# Aux_Board_V2_1.net
KiCad netlist of a schematic drawn in EAGLE
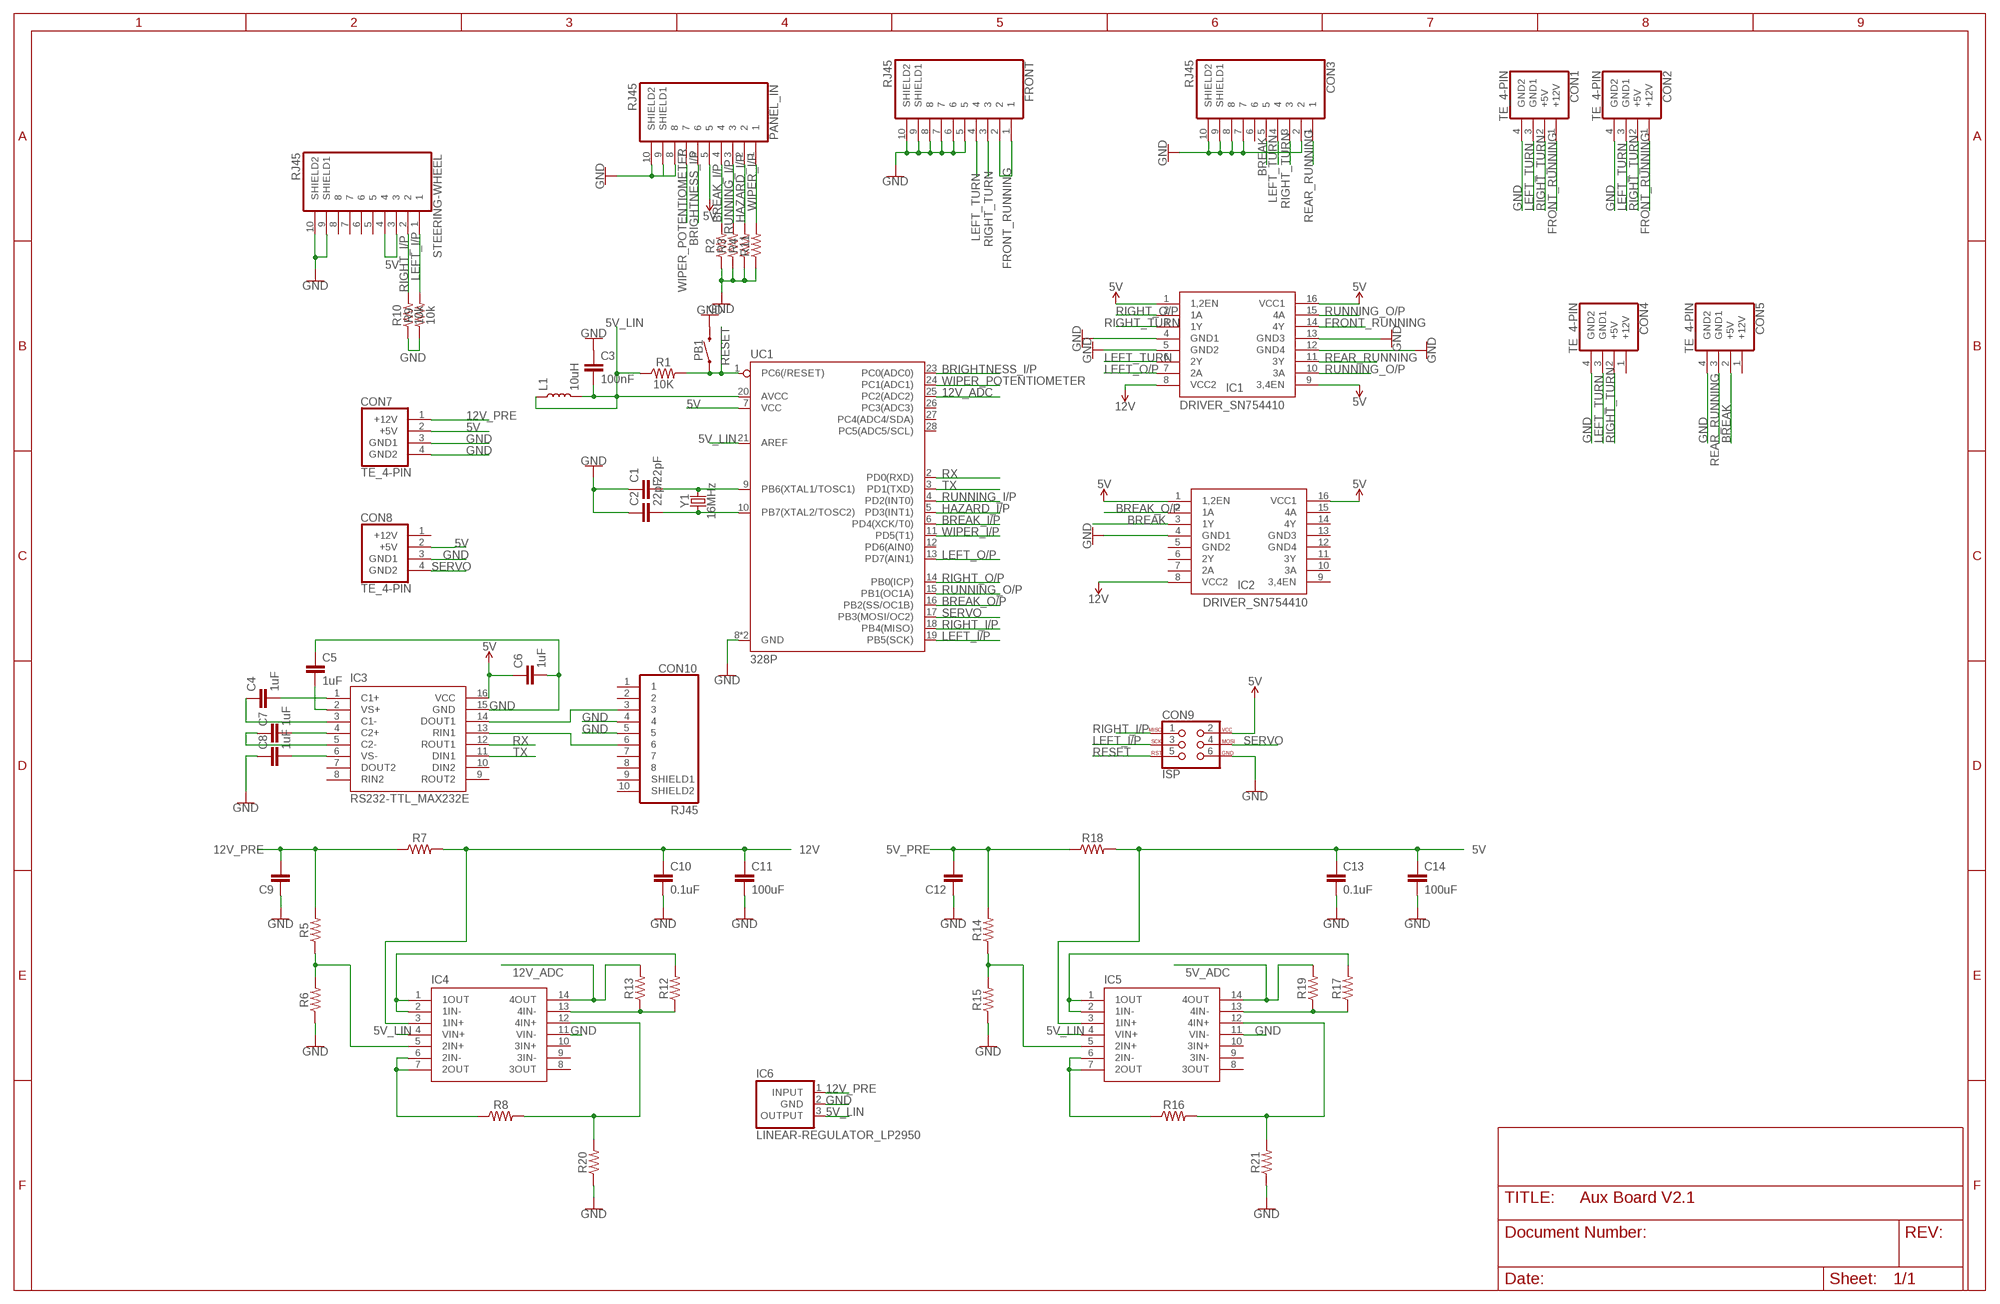
[diagram p0: schematic, sheet 1]

(export (version "E")
  (design (tool "Eeschema 10.0.6"))
  (components
    (comp (ref "C1")
      (value "22pF")
      (footprint "eagle-import:0805")
      (libsource (lib "eagle-import") (part "CAPACITOR_0805"))
    )
    (comp (ref "C2")
      (value "22pF")
      (footprint "eagle-import:0805")
      (libsource (lib "eagle-import") (part "CAPACITOR_0805"))
    )
    (comp (ref "C3")
      (value "100nF")
      (footprint "eagle-import:0805")
      (libsource (lib "eagle-import") (part "CAPACITOR_0805"))
    )
    (comp (ref "C4")
      (value "1uF")
      (footprint "eagle-import:0805")
      (libsource (lib "eagle-import") (part "CAPACITOR_0805"))
    )
    (comp (ref "C5")
      (value "1uF")
      (footprint "eagle-import:0805")
      (libsource (lib "eagle-import") (part "CAPACITOR_0805"))
    )
    (comp (ref "C6")
      (value "1uF")
      (footprint "eagle-import:0805")
      (libsource (lib "eagle-import") (part "CAPACITOR_0805"))
    )
    (comp (ref "C7")
      (value "1uF")
      (footprint "eagle-import:0805")
      (libsource (lib "eagle-import") (part "CAPACITOR_0805"))
    )
    (comp (ref "C8")
      (value "1uF")
      (footprint "eagle-import:0805")
      (libsource (lib "eagle-import") (part "CAPACITOR_0805"))
    )
    (comp (ref "C9")
      (value "CAPACITOR_0805")
      (footprint "eagle-import:0805")
      (libsource (lib "eagle-import") (part "CAPACITOR_0805"))
    )
    (comp (ref "C10")
      (value "0.1uF")
      (footprint "eagle-import:0805")
      (libsource (lib "eagle-import") (part "CAPACITOR_0805"))
    )
    (comp (ref "C11")
      (value "100uF")
      (footprint "eagle-import:0805")
      (libsource (lib "eagle-import") (part "CAPACITOR_0805"))
    )
    (comp (ref "C12")
      (value "CAPACITOR_0805")
      (footprint "eagle-import:0805")
      (libsource (lib "eagle-import") (part "CAPACITOR_0805"))
    )
    (comp (ref "C13")
      (value "0.1uF")
      (footprint "eagle-import:0805")
      (libsource (lib "eagle-import") (part "CAPACITOR_0805"))
    )
    (comp (ref "C14")
      (value "100uF")
      (footprint "eagle-import:0805")
      (libsource (lib "eagle-import") (part "CAPACITOR_0805"))
    )
    (comp (ref "CON1")
      (value "TE_4-PIN")
      (footprint "eagle-import:TE_4-PIN")
      (libsource (lib "eagle-import") (part "TE_4-PIN"))
    )
    (comp (ref "CON2")
      (value "TE_4-PIN")
      (footprint "eagle-import:TE_4-PIN")
      (libsource (lib "eagle-import") (part "TE_4-PIN"))
    )
    (comp (ref "CON3")
      (value "RJ45")
      (footprint "eagle-import:RJ45")
      (libsource (lib "eagle-import") (part "RJ45"))
    )
    (comp (ref "CON4")
      (value "TE_4-PIN")
      (footprint "eagle-import:TE_4-PIN")
      (libsource (lib "eagle-import") (part "TE_4-PIN"))
    )
    (comp (ref "CON5")
      (value "TE_4-PIN")
      (footprint "eagle-import:TE_4-PIN")
      (libsource (lib "eagle-import") (part "TE_4-PIN"))
    )
    (comp (ref "CON7")
      (value "TE_4-PIN")
      (footprint "eagle-import:TE_4-PIN")
      (libsource (lib "eagle-import") (part "TE_4-PIN"))
    )
    (comp (ref "CON8")
      (value "TE_4-PIN")
      (footprint "eagle-import:TE_4-PIN")
      (libsource (lib "eagle-import") (part "TE_4-PIN"))
    )
    (comp (ref "CON9")
      (value "ISP")
      (footprint "eagle-import:ISP_CONNECTOR")
      (libsource (lib "eagle-import") (part "ISP"))
    )
    (comp (ref "CON10")
      (value "RJ45")
      (footprint "eagle-import:RJ45")
      (libsource (lib "eagle-import") (part "RJ45"))
    )
    (comp (ref "FRONT")
      (value "RJ45")
      (footprint "eagle-import:RJ45")
      (libsource (lib "eagle-import") (part "RJ45"))
    )
    (comp (ref "IC1")
      (value "DRIVER_SN754410")
      (footprint "eagle-import:DIP16")
      (libsource (lib "eagle-import") (part "DRIVER_SN754410"))
    )
    (comp (ref "IC2")
      (value "DRIVER_SN754410")
      (footprint "eagle-import:DIP16")
      (libsource (lib "eagle-import") (part "DRIVER_SN754410"))
    )
    (comp (ref "IC3")
      (value "RS232-TTL_MAX232E")
      (footprint "eagle-import:DIP16")
      (libsource (lib "eagle-import") (part "RS232-TTL_MAX232E"))
    )
    (comp (ref "IC4")
      (value "OP-AMP_QUAD")
      (footprint "eagle-import:DIP14")
      (libsource (lib "eagle-import") (part "OP-AMP_QUAD"))
    )
    (comp (ref "IC5")
      (value "OP-AMP_QUAD")
      (footprint "eagle-import:DIP14")
      (libsource (lib "eagle-import") (part "OP-AMP_QUAD"))
    )
    (comp (ref "IC6")
      (value "LINEAR-REGULATOR_LP2950")
      (footprint "eagle-import:TO92")
      (libsource (lib "eagle-import") (part "LINEAR-REGULATOR_LP2950"))
    )
    (comp (ref "L1")
      (value "10uH")
      (footprint "eagle-import:0805")
      (libsource (lib "eagle-import") (part "INDUCTOR_0805"))
    )
    (comp (ref "PANEL_IN")
      (value "RJ45")
      (footprint "eagle-import:RJ45")
      (libsource (lib "eagle-import") (part "RJ45"))
    )
    (comp (ref "PB1")
      (value "PUSHBUTTON")
      (footprint "eagle-import:PUSHBUTTON")
      (libsource (lib "eagle-import") (part "PUSHBUTTON"))
    )
    (comp (ref "R1")
      (value "10K")
      (footprint "eagle-import:0805")
      (libsource (lib "eagle-import") (part "RESISTOR_0805"))
    )
    (comp (ref "R2")
      (value "RESISTOR_0805")
      (footprint "eagle-import:0805")
      (libsource (lib "eagle-import") (part "RESISTOR_0805"))
    )
    (comp (ref "R3")
      (value "RESISTOR_0805")
      (footprint "eagle-import:0805")
      (libsource (lib "eagle-import") (part "RESISTOR_0805"))
    )
    (comp (ref "R4")
      (value "RESISTOR_0805")
      (footprint "eagle-import:0805")
      (libsource (lib "eagle-import") (part "RESISTOR_0805"))
    )
    (comp (ref "R5")
      (value "RESISTOR_0805")
      (footprint "eagle-import:0805")
      (libsource (lib "eagle-import") (part "RESISTOR_0805"))
    )
    (comp (ref "R6")
      (value "RESISTOR_0805")
      (footprint "eagle-import:0805")
      (libsource (lib "eagle-import") (part "RESISTOR_0805"))
    )
    (comp (ref "R7")
      (value "RESISTOR_1210")
      (footprint "eagle-import:1210")
      (libsource (lib "eagle-import") (part "RESISTOR_1210"))
    )
    (comp (ref "R8")
      (value "RESISTOR_0805")
      (footprint "eagle-import:0805")
      (libsource (lib "eagle-import") (part "RESISTOR_0805"))
    )
    (comp (ref "R9")
      (value "10k")
      (footprint "eagle-import:0805")
      (libsource (lib "eagle-import") (part "RESISTOR_0805"))
    )
    (comp (ref "R10")
      (value "10k")
      (footprint "eagle-import:0805")
      (libsource (lib "eagle-import") (part "RESISTOR_0805"))
    )
    (comp (ref "R11")
      (value "RESISTOR_0805")
      (footprint "eagle-import:0805")
      (libsource (lib "eagle-import") (part "RESISTOR_0805"))
    )
    (comp (ref "R12")
      (value "RESISTOR_0805")
      (footprint "eagle-import:0805")
      (libsource (lib "eagle-import") (part "RESISTOR_0805"))
    )
    (comp (ref "R13")
      (value "RESISTOR_0805")
      (footprint "eagle-import:0805")
      (libsource (lib "eagle-import") (part "RESISTOR_0805"))
    )
    (comp (ref "R14")
      (value "RESISTOR_0805")
      (footprint "eagle-import:0805")
      (libsource (lib "eagle-import") (part "RESISTOR_0805"))
    )
    (comp (ref "R15")
      (value "RESISTOR_0805")
      (footprint "eagle-import:0805")
      (libsource (lib "eagle-import") (part "RESISTOR_0805"))
    )
    (comp (ref "R16")
      (value "RESISTOR_0805")
      (footprint "eagle-import:0805")
      (libsource (lib "eagle-import") (part "RESISTOR_0805"))
    )
    (comp (ref "R17")
      (value "RESISTOR_0805")
      (footprint "eagle-import:0805")
      (libsource (lib "eagle-import") (part "RESISTOR_0805"))
    )
    (comp (ref "R18")
      (value "RESISTOR_1210")
      (footprint "eagle-import:1210")
      (libsource (lib "eagle-import") (part "RESISTOR_1210"))
    )
    (comp (ref "R19")
      (value "RESISTOR_0805")
      (footprint "eagle-import:0805")
      (libsource (lib "eagle-import") (part "RESISTOR_0805"))
    )
    (comp (ref "R20")
      (value "RESISTOR_0805")
      (footprint "eagle-import:0805")
      (libsource (lib "eagle-import") (part "RESISTOR_0805"))
    )
    (comp (ref "R21")
      (value "RESISTOR_0805")
      (footprint "eagle-import:0805")
      (libsource (lib "eagle-import") (part "RESISTOR_0805"))
    )
    (comp (ref "STEERING-WHEEL")
      (value "RJ45")
      (footprint "eagle-import:RJ45")
      (libsource (lib "eagle-import") (part "RJ45"))
    )
    (comp (ref "UC1")
      (value "328P")
      (footprint "eagle-import:DIP28")
      (libsource (lib "eagle-import") (part "ATMEGA328P_DIP28"))
    )
    (comp (ref "Y1")
      (value "16MHz")
      (footprint "eagle-import:HC49US")
      (libsource (lib "eagle-import") (part "CRYSTAL-16MHZPTH-HC49US"))
    )
  )
  (nets
    (net (code "1") (name "/5V_ADC") (class "Default")
      (node (ref "IC5") (pin "14") (pinfunction "4OUT_14") (pintype "bidirectional"))
      (node (ref "R19") (pin "2") (pinfunction "2_2") (pintype "passive"))
    )
    (net (code "2") (name "/5V_LIN") (class "Default")
      (node (ref "C3") (pin "2") (pinfunction "2_2") (pintype "passive"))
      (node (ref "IC4") (pin "4") (pinfunction "VIN+_4") (pintype "bidirectional"))
      (node (ref "IC5") (pin "4") (pinfunction "VIN+_4") (pintype "bidirectional"))
      (node (ref "IC6") (pin "3") (pinfunction "OUTPUT_3") (pintype "bidirectional"))
      (node (ref "L1") (pin "1") (pinfunction "1_1") (pintype "passive"))
      (node (ref "L1") (pin "2") (pinfunction "2_2") (pintype "passive"))
      (node (ref "R1") (pin "1") (pinfunction "1_1") (pintype "passive"))
      (node (ref "UC1") (pin "20") (pinfunction "AVCC_20") (pintype "bidirectional"))
      (node (ref "UC1") (pin "21") (pinfunction "AREF_21") (pintype "bidirectional"))
    )
    (net (code "3") (name "/5V_PRE") (class "Default")
      (node (ref "C12") (pin "2") (pinfunction "2_2") (pintype "passive"))
      (node (ref "R14") (pin "2") (pinfunction "2_2") (pintype "passive"))
      (node (ref "R18") (pin "1") (pinfunction "1_1") (pintype "passive"))
    )
    (net (code "4") (name "/12V_ADC") (class "Default")
      (node (ref "IC4") (pin "14") (pinfunction "4OUT_14") (pintype "bidirectional"))
      (node (ref "R13") (pin "2") (pinfunction "2_2") (pintype "passive"))
      (node (ref "UC1") (pin "25") (pinfunction "PC2(ADC2)_25") (pintype "bidirectional"))
    )
    (net (code "5") (name "/12V_PRE") (class "Default")
      (node (ref "C9") (pin "2") (pinfunction "2_2") (pintype "passive"))
      (node (ref "CON7") (pin "1") (pinfunction "+12V_1") (pintype "passive"))
      (node (ref "IC6") (pin "1") (pinfunction "INPUT_1") (pintype "bidirectional"))
      (node (ref "R5") (pin "2") (pinfunction "2_2") (pintype "passive"))
      (node (ref "R7") (pin "1") (pinfunction "1_1") (pintype "passive"))
    )
    (net (code "6") (name "/BREAK") (class "Default")
      (node (ref "CON3") (pin "5") (pinfunction "5_5") (pintype "passive"))
      (node (ref "CON5") (pin "2") (pinfunction "+5V_2") (pintype "passive"))
      (node (ref "IC2") (pin "3") (pinfunction "1Y_3") (pintype "bidirectional"))
    )
    (net (code "7") (name "/BREAK_I{slash}P") (class "Default")
      (node (ref "PANEL_IN") (pin "4") (pinfunction "4_4") (pintype "passive"))
      (node (ref "R2") (pin "2") (pinfunction "2_2") (pintype "passive"))
      (node (ref "UC1") (pin "6") (pinfunction "PD4(XCK/T0)_6") (pintype "bidirectional"))
    )
    (net (code "8") (name "/BREAK_O{slash}P") (class "Default")
      (node (ref "IC2") (pin "2") (pinfunction "1A_2") (pintype "bidirectional"))
      (node (ref "UC1") (pin "16") (pinfunction "PB2(SS/OC1B)_16") (pintype "bidirectional"))
    )
    (net (code "9") (name "/BRIGHTNESS_I{slash}P") (class "Default")
      (node (ref "PANEL_IN") (pin "6") (pinfunction "6_6") (pintype "passive"))
      (node (ref "UC1") (pin "23") (pinfunction "PC0(ADC0)_23") (pintype "bidirectional"))
    )
    (net (code "10") (name "/FRONT_RUNNING") (class "Default")
      (node (ref "CON1") (pin "1") (pinfunction "+12V_1") (pintype "passive"))
      (node (ref "CON2") (pin "1") (pinfunction "+12V_1") (pintype "passive"))
      (node (ref "FRONT") (pin "1") (pinfunction "1_1") (pintype "passive"))
      (node (ref "FRONT") (pin "2") (pinfunction "2_2") (pintype "passive"))
      (node (ref "IC1") (pin "14") (pinfunction "4Y_14") (pintype "bidirectional"))
    )
    (net (code "11") (name "/HAZARD_I{slash}P") (class "Default")
      (node (ref "PANEL_IN") (pin "2") (pinfunction "2_2") (pintype "passive"))
      (node (ref "R4") (pin "2") (pinfunction "2_2") (pintype "passive"))
      (node (ref "UC1") (pin "5") (pinfunction "PD3(INT1)_5") (pintype "bidirectional"))
    )
    (net (code "12") (name "/LEFT_I{slash}P") (class "Default")
      (node (ref "CON9") (pin "3") (pinfunction "3_3") (pintype "passive"))
      (node (ref "R9") (pin "2") (pinfunction "2_2") (pintype "passive"))
      (node (ref "STEERING-WHEEL") (pin "1") (pinfunction "1_1") (pintype "passive"))
      (node (ref "UC1") (pin "19") (pinfunction "PB5(SCK)_19") (pintype "bidirectional"))
    )
    (net (code "13") (name "/LEFT_O{slash}P") (class "Default")
      (node (ref "IC1") (pin "7") (pinfunction "2A_7") (pintype "bidirectional"))
      (node (ref "UC1") (pin "13") (pinfunction "PD7(AIN1)_13") (pintype "bidirectional"))
    )
    (net (code "14") (name "/LEFT_TURN") (class "Default")
      (node (ref "CON1") (pin "3") (pinfunction "GND1_3") (pintype "passive"))
      (node (ref "CON2") (pin "3") (pinfunction "GND1_3") (pintype "passive"))
      (node (ref "CON3") (pin "4") (pinfunction "4_4") (pintype "passive"))
      (node (ref "CON4") (pin "3") (pinfunction "GND1_3") (pintype "passive"))
      (node (ref "FRONT") (pin "4") (pinfunction "4_4") (pintype "passive"))
      (node (ref "IC1") (pin "6") (pinfunction "2Y_6") (pintype "bidirectional"))
    )
    (net (code "15") (name "/REAR_RUNNING") (class "Default")
      (node (ref "CON3") (pin "1") (pinfunction "1_1") (pintype "passive"))
      (node (ref "CON5") (pin "3") (pinfunction "GND1_3") (pintype "passive"))
      (node (ref "IC1") (pin "11") (pinfunction "3Y_11") (pintype "bidirectional"))
    )
    (net (code "16") (name "/RESET") (class "Default")
      (node (ref "CON9") (pin "5") (pinfunction "5_5") (pintype "passive"))
      (node (ref "PB1") (pin "1") (pinfunction "1_1") (pintype "passive"))
      (node (ref "PB1") (pin "2") (pinfunction "1_2") (pintype "passive"))
      (node (ref "R1") (pin "2") (pinfunction "2_2") (pintype "passive"))
      (node (ref "UC1") (pin "1") (pinfunction "PC6(/RESET)_1") (pintype "bidirectional"))
    )
    (net (code "17") (name "/RIGHT_I{slash}P") (class "Default")
      (node (ref "CON9") (pin "1") (pinfunction "1_1") (pintype "passive"))
      (node (ref "R10") (pin "2") (pinfunction "2_2") (pintype "passive"))
      (node (ref "STEERING-WHEEL") (pin "2") (pinfunction "2_2") (pintype "passive"))
      (node (ref "UC1") (pin "18") (pinfunction "PB4(MISO)_18") (pintype "bidirectional"))
    )
    (net (code "18") (name "/RIGHT_O{slash}P") (class "Default")
      (node (ref "IC1") (pin "2") (pinfunction "1A_2") (pintype "bidirectional"))
      (node (ref "UC1") (pin "14") (pinfunction "PB0(ICP)_14") (pintype "bidirectional"))
    )
    (net (code "19") (name "/RIGHT_TURN") (class "Default")
      (node (ref "CON1") (pin "2") (pinfunction "+5V_2") (pintype "passive"))
      (node (ref "CON2") (pin "2") (pinfunction "+5V_2") (pintype "passive"))
      (node (ref "CON3") (pin "3") (pinfunction "3_3") (pintype "passive"))
      (node (ref "CON4") (pin "2") (pinfunction "+5V_2") (pintype "passive"))
      (node (ref "FRONT") (pin "3") (pinfunction "3_3") (pintype "passive"))
      (node (ref "IC1") (pin "3") (pinfunction "1Y_3") (pintype "bidirectional"))
    )
    (net (code "20") (name "/RUNNING_I{slash}P") (class "Default")
      (node (ref "PANEL_IN") (pin "3") (pinfunction "3_3") (pintype "passive"))
      (node (ref "R3") (pin "2") (pinfunction "2_2") (pintype "passive"))
      (node (ref "UC1") (pin "4") (pinfunction "PD2(INT0)_4") (pintype "bidirectional"))
    )
    (net (code "21") (name "/RUNNING_O{slash}P") (class "Default")
      (node (ref "IC1") (pin "10") (pinfunction "3A_10") (pintype "bidirectional"))
      (node (ref "IC1") (pin "15") (pinfunction "4A_15") (pintype "bidirectional"))
      (node (ref "UC1") (pin "15") (pinfunction "PB1(OC1A)_15") (pintype "bidirectional"))
    )
    (net (code "22") (name "/RX") (class "Default")
      (node (ref "IC3") (pin "12") (pinfunction "ROUT1_12") (pintype "bidirectional"))
      (node (ref "UC1") (pin "2") (pinfunction "PD0(RXD)_2") (pintype "bidirectional"))
    )
    (net (code "23") (name "/SERVO") (class "Default")
      (node (ref "CON8") (pin "4") (pinfunction "GND2_4") (pintype "passive"))
      (node (ref "CON9") (pin "4") (pinfunction "4_4") (pintype "passive"))
      (node (ref "UC1") (pin "17") (pinfunction "PB3(MOSI/OC2)_17") (pintype "bidirectional"))
    )
    (net (code "24") (name "/TX") (class "Default")
      (node (ref "IC3") (pin "11") (pinfunction "DIN1_11") (pintype "bidirectional"))
      (node (ref "UC1") (pin "3") (pinfunction "PD1(TXD)_3") (pintype "bidirectional"))
    )
    (net (code "25") (name "/WIPER_I{slash}P") (class "Default")
      (node (ref "PANEL_IN") (pin "1") (pinfunction "1_1") (pintype "passive"))
      (node (ref "R11") (pin "2") (pinfunction "2_2") (pintype "passive"))
      (node (ref "UC1") (pin "11") (pinfunction "PD5(T1)_11") (pintype "bidirectional"))
    )
    (net (code "26") (name "/WIPER_POTENTIOMETER") (class "Default")
      (node (ref "PANEL_IN") (pin "7") (pinfunction "7_7") (pintype "passive"))
      (node (ref "UC1") (pin "24") (pinfunction "PC1(ADC1)_24") (pintype "bidirectional"))
    )
    (net (code "27") (name "5V") (class "Default")
      (node (ref "C13") (pin "1") (pinfunction "1_1") (pintype "passive"))
      (node (ref "C14") (pin "1") (pinfunction "1_1") (pintype "passive"))
      (node (ref "C6") (pin "1") (pinfunction "1_1") (pintype "passive"))
      (node (ref "CON7") (pin "2") (pinfunction "+5V_2") (pintype "passive"))
      (node (ref "CON8") (pin "2") (pinfunction "+5V_2") (pintype "passive"))
      (node (ref "CON9") (pin "2") (pinfunction "2_2") (pintype "passive"))
      (node (ref "IC1") (pin "1") (pinfunction "1,2EN_1") (pintype "bidirectional"))
      (node (ref "IC1") (pin "16") (pinfunction "VCC1_16") (pintype "bidirectional"))
      (node (ref "IC1") (pin "9") (pinfunction "3,4EN_9") (pintype "bidirectional"))
      (node (ref "IC2") (pin "1") (pinfunction "1,2EN_1") (pintype "bidirectional"))
      (node (ref "IC2") (pin "16") (pinfunction "VCC1_16") (pintype "bidirectional"))
      (node (ref "IC3") (pin "16") (pinfunction "VCC_16") (pintype "bidirectional"))
      (node (ref "IC5") (pin "3") (pinfunction "1IN+_3") (pintype "bidirectional"))
      (node (ref "PANEL_IN") (pin "5") (pinfunction "5_5") (pintype "passive"))
      (node (ref "R18") (pin "2") (pinfunction "2_2") (pintype "passive"))
      (node (ref "STEERING-WHEEL") (pin "3") (pinfunction "3_3") (pintype "passive"))
      (node (ref "STEERING-WHEEL") (pin "4") (pinfunction "4_4") (pintype "passive"))
      (node (ref "UC1") (pin "7") (pinfunction "VCC_7") (pintype "bidirectional"))
    )
    (net (code "28") (name "12V") (class "Default")
      (node (ref "C10") (pin "1") (pinfunction "1_1") (pintype "passive"))
      (node (ref "C11") (pin "1") (pinfunction "1_1") (pintype "passive"))
      (node (ref "IC1") (pin "8") (pinfunction "VCC2_8") (pintype "bidirectional"))
      (node (ref "IC2") (pin "8") (pinfunction "VCC2_8") (pintype "bidirectional"))
      (node (ref "IC4") (pin "3") (pinfunction "1IN+_3") (pintype "bidirectional"))
      (node (ref "R7") (pin "2") (pinfunction "2_2") (pintype "passive"))
    )
    (net (code "29") (name "GND") (class "Default")
      (node (ref "C1") (pin "1") (pinfunction "1_1") (pintype "passive"))
      (node (ref "C10") (pin "2") (pinfunction "2_2") (pintype "passive"))
      (node (ref "C11") (pin "2") (pinfunction "2_2") (pintype "passive"))
      (node (ref "C12") (pin "1") (pinfunction "1_1") (pintype "passive"))
      (node (ref "C13") (pin "2") (pinfunction "2_2") (pintype "passive"))
      (node (ref "C14") (pin "2") (pinfunction "2_2") (pintype "passive"))
      (node (ref "C2") (pin "1") (pinfunction "1_1") (pintype "passive"))
      (node (ref "C3") (pin "1") (pinfunction "1_1") (pintype "passive"))
      (node (ref "C5") (pin "1") (pinfunction "1_1") (pintype "passive"))
      (node (ref "C6") (pin "2") (pinfunction "2_2") (pintype "passive"))
      (node (ref "C8") (pin "1") (pinfunction "1_1") (pintype "passive"))
      (node (ref "C9") (pin "1") (pinfunction "1_1") (pintype "passive"))
      (node (ref "CON1") (pin "4") (pinfunction "GND2_4") (pintype "passive"))
      (node (ref "CON10") (pin "4") (pinfunction "4_4") (pintype "passive"))
      (node (ref "CON10") (pin "5") (pinfunction "5_5") (pintype "passive"))
      (node (ref "CON2") (pin "4") (pinfunction "GND2_4") (pintype "passive"))
      (node (ref "CON3") (pin "10") (pinfunction "SHIELD2_10") (pintype "passive"))
      (node (ref "CON3") (pin "2") (pinfunction "2_2") (pintype "passive"))
      (node (ref "CON3") (pin "7") (pinfunction "7_7") (pintype "passive"))
      (node (ref "CON3") (pin "8") (pinfunction "8_8") (pintype "passive"))
      (node (ref "CON3") (pin "9") (pinfunction "SHIELD1_9") (pintype "passive"))
      (node (ref "CON4") (pin "4") (pinfunction "GND2_4") (pintype "passive"))
      (node (ref "CON5") (pin "4") (pinfunction "GND2_4") (pintype "passive"))
      (node (ref "CON7") (pin "3") (pinfunction "GND1_3") (pintype "passive"))
      (node (ref "CON7") (pin "4") (pinfunction "GND2_4") (pintype "passive"))
      (node (ref "CON8") (pin "3") (pinfunction "GND1_3") (pintype "passive"))
      (node (ref "CON9") (pin "6") (pinfunction "6_6") (pintype "passive"))
      (node (ref "FRONT") (pin "10") (pinfunction "SHIELD2_10") (pintype "passive"))
      (node (ref "FRONT") (pin "5") (pinfunction "5_5") (pintype "passive"))
      (node (ref "FRONT") (pin "6") (pinfunction "6_6") (pintype "passive"))
      (node (ref "FRONT") (pin "7") (pinfunction "7_7") (pintype "passive"))
      (node (ref "FRONT") (pin "8") (pinfunction "8_8") (pintype "passive"))
      (node (ref "FRONT") (pin "9") (pinfunction "SHIELD1_9") (pintype "passive"))
      (node (ref "IC1") (pin "12") (pinfunction "GND4_12") (pintype "bidirectional"))
      (node (ref "IC1") (pin "13") (pinfunction "GND3_13") (pintype "bidirectional"))
      (node (ref "IC1") (pin "4") (pinfunction "GND1_4") (pintype "bidirectional"))
      (node (ref "IC1") (pin "5") (pinfunction "GND2_5") (pintype "bidirectional"))
      (node (ref "IC2") (pin "4") (pinfunction "GND1_4") (pintype "bidirectional"))
      (node (ref "IC3") (pin "15") (pinfunction "GND_15") (pintype "bidirectional"))
      (node (ref "IC4") (pin "11") (pinfunction "VIN-_11") (pintype "bidirectional"))
      (node (ref "IC5") (pin "11") (pinfunction "VIN-_11") (pintype "bidirectional"))
      (node (ref "IC6") (pin "2") (pinfunction "GND_2") (pintype "bidirectional"))
      (node (ref "PANEL_IN") (pin "10") (pinfunction "SHIELD2_10") (pintype "passive"))
      (node (ref "PANEL_IN") (pin "8") (pinfunction "8_8") (pintype "passive"))
      (node (ref "PANEL_IN") (pin "9") (pinfunction "SHIELD1_9") (pintype "passive"))
      (node (ref "PB1") (pin "3") (pinfunction "2_3") (pintype "passive"))
      (node (ref "PB1") (pin "4") (pinfunction "2_4") (pintype "passive"))
      (node (ref "R10") (pin "1") (pinfunction "1_1") (pintype "passive"))
      (node (ref "R11") (pin "1") (pinfunction "1_1") (pintype "passive"))
      (node (ref "R15") (pin "1") (pinfunction "1_1") (pintype "passive"))
      (node (ref "R2") (pin "1") (pinfunction "1_1") (pintype "passive"))
      (node (ref "R20") (pin "1") (pinfunction "1_1") (pintype "passive"))
      (node (ref "R21") (pin "1") (pinfunction "1_1") (pintype "passive"))
      (node (ref "R3") (pin "1") (pinfunction "1_1") (pintype "passive"))
      (node (ref "R4") (pin "1") (pinfunction "1_1") (pintype "passive"))
      (node (ref "R6") (pin "1") (pinfunction "1_1") (pintype "passive"))
      (node (ref "R9") (pin "1") (pinfunction "1_1") (pintype "passive"))
      (node (ref "STEERING-WHEEL") (pin "10") (pinfunction "SHIELD2_10") (pintype "passive"))
      (node (ref "STEERING-WHEEL") (pin "9") (pinfunction "SHIELD1_9") (pintype "passive"))
      (node (ref "UC1") (pin "22") (pinfunction "GND_22") (pintype "bidirectional"))
      (node (ref "UC1") (pin "8") (pinfunction "GND_8") (pintype "bidirectional"))
    )
    (net (code "30") (name "Net-(IC3-C1+)") (class "Default")
      (node (ref "C4") (pin "2") (pinfunction "2_2") (pintype "passive"))
      (node (ref "IC3") (pin "1") (pinfunction "C1+_1") (pintype "bidirectional"))
    )
    (net (code "31") (name "Net-(IC3-C1-)") (class "Default")
      (node (ref "C4") (pin "1") (pinfunction "1_1") (pintype "passive"))
      (node (ref "IC3") (pin "3") (pinfunction "C1-_3") (pintype "bidirectional"))
    )
    (net (code "32") (name "Net-(IC3-C2+)") (class "Default")
      (node (ref "C7") (pin "2") (pinfunction "2_2") (pintype "passive"))
      (node (ref "IC3") (pin "4") (pinfunction "C2+_4") (pintype "bidirectional"))
    )
    (net (code "33") (name "Net-(IC3-C2-)") (class "Default")
      (node (ref "C7") (pin "1") (pinfunction "1_1") (pintype "passive"))
      (node (ref "IC3") (pin "5") (pinfunction "C2-_5") (pintype "bidirectional"))
    )
    (net (code "34") (name "Net-(IC3-DOUT1)") (class "Default")
      (node (ref "CON10") (pin "3") (pinfunction "3_3") (pintype "passive"))
      (node (ref "IC3") (pin "14") (pinfunction "DOUT1_14") (pintype "bidirectional"))
    )
    (net (code "35") (name "Net-(IC3-RIN1)") (class "Default")
      (node (ref "CON10") (pin "6") (pinfunction "6_6") (pintype "passive"))
      (node (ref "IC3") (pin "13") (pinfunction "RIN1_13") (pintype "bidirectional"))
    )
    (net (code "36") (name "Net-(IC3-VS+)") (class "Default")
      (node (ref "C5") (pin "2") (pinfunction "2_2") (pintype "passive"))
      (node (ref "IC3") (pin "2") (pinfunction "VS+_2") (pintype "bidirectional"))
    )
    (net (code "37") (name "Net-(IC3-VS-)") (class "Default")
      (node (ref "C8") (pin "2") (pinfunction "2_2") (pintype "passive"))
      (node (ref "IC3") (pin "6") (pinfunction "VS-_6") (pintype "bidirectional"))
    )
    (net (code "38") (name "Net-(IC4-1IN-)") (class "Default")
      (node (ref "IC4") (pin "1") (pinfunction "1OUT_1") (pintype "bidirectional"))
      (node (ref "IC4") (pin "2") (pinfunction "1IN-_2") (pintype "bidirectional"))
      (node (ref "R12") (pin "2") (pinfunction "2_2") (pintype "passive"))
    )
    (net (code "39") (name "Net-(IC4-2IN+)") (class "Default")
      (node (ref "IC4") (pin "5") (pinfunction "2IN+_5") (pintype "bidirectional"))
      (node (ref "R5") (pin "1") (pinfunction "1_1") (pintype "passive"))
      (node (ref "R6") (pin "2") (pinfunction "2_2") (pintype "passive"))
    )
    (net (code "40") (name "Net-(IC4-2IN-)") (class "Default")
      (node (ref "IC4") (pin "6") (pinfunction "2IN-_6") (pintype "bidirectional"))
      (node (ref "IC4") (pin "7") (pinfunction "2OUT_7") (pintype "bidirectional"))
      (node (ref "R8") (pin "1") (pinfunction "1_1") (pintype "passive"))
    )
    (net (code "41") (name "Net-(IC4-4IN+)") (class "Default")
      (node (ref "IC4") (pin "12") (pinfunction "4IN+_12") (pintype "bidirectional"))
      (node (ref "R20") (pin "2") (pinfunction "2_2") (pintype "passive"))
      (node (ref "R8") (pin "2") (pinfunction "2_2") (pintype "passive"))
    )
    (net (code "42") (name "Net-(IC4-4IN-)") (class "Default")
      (node (ref "IC4") (pin "13") (pinfunction "4IN-_13") (pintype "bidirectional"))
      (node (ref "R12") (pin "1") (pinfunction "1_1") (pintype "passive"))
      (node (ref "R13") (pin "1") (pinfunction "1_1") (pintype "passive"))
    )
    (net (code "43") (name "Net-(IC5-1IN-)") (class "Default")
      (node (ref "IC5") (pin "1") (pinfunction "1OUT_1") (pintype "bidirectional"))
      (node (ref "IC5") (pin "2") (pinfunction "1IN-_2") (pintype "bidirectional"))
      (node (ref "R17") (pin "2") (pinfunction "2_2") (pintype "passive"))
    )
    (net (code "44") (name "Net-(IC5-2IN+)") (class "Default")
      (node (ref "IC5") (pin "5") (pinfunction "2IN+_5") (pintype "bidirectional"))
      (node (ref "R14") (pin "1") (pinfunction "1_1") (pintype "passive"))
      (node (ref "R15") (pin "2") (pinfunction "2_2") (pintype "passive"))
    )
    (net (code "45") (name "Net-(IC5-2IN-)") (class "Default")
      (node (ref "IC5") (pin "6") (pinfunction "2IN-_6") (pintype "bidirectional"))
      (node (ref "IC5") (pin "7") (pinfunction "2OUT_7") (pintype "bidirectional"))
      (node (ref "R16") (pin "1") (pinfunction "1_1") (pintype "passive"))
    )
    (net (code "46") (name "Net-(IC5-4IN+)") (class "Default")
      (node (ref "IC5") (pin "12") (pinfunction "4IN+_12") (pintype "bidirectional"))
      (node (ref "R16") (pin "2") (pinfunction "2_2") (pintype "passive"))
      (node (ref "R21") (pin "2") (pinfunction "2_2") (pintype "passive"))
    )
    (net (code "47") (name "Net-(IC5-4IN-)") (class "Default")
      (node (ref "IC5") (pin "13") (pinfunction "4IN-_13") (pintype "bidirectional"))
      (node (ref "R17") (pin "1") (pinfunction "1_1") (pintype "passive"))
      (node (ref "R19") (pin "1") (pinfunction "1_1") (pintype "passive"))
    )
    (net (code "48") (name "Net-(UC1-PB6(XTAL1{slash}TOSC1))") (class "Default")
      (node (ref "C1") (pin "2") (pinfunction "2_2") (pintype "passive"))
      (node (ref "UC1") (pin "9") (pinfunction "PB6(XTAL1/TOSC1)_9") (pintype "bidirectional"))
      (node (ref "Y1") (pin "2") (pinfunction "2_2") (pintype "passive"))
    )
    (net (code "49") (name "Net-(UC1-PB7(XTAL2{slash}TOSC2))") (class "Default")
      (node (ref "C2") (pin "2") (pinfunction "2_2") (pintype "passive"))
      (node (ref "UC1") (pin "10") (pinfunction "PB7(XTAL2/TOSC2)_10") (pintype "bidirectional"))
      (node (ref "Y1") (pin "1") (pinfunction "1_1") (pintype "passive"))
    )
    (net (code "50") (name "unconnected-(CON3-Pad6)") (class "Default")
      (node (ref "CON3") (pin "6") (pinfunction "6_6") (pintype "passive"))
    )
    (net (code "51") (name "unconnected-(CON4-+12V-Pad1)") (class "Default")
      (node (ref "CON4") (pin "1") (pinfunction "+12V_1") (pintype "passive"))
    )
    (net (code "52") (name "unconnected-(CON5-+12V-Pad1)") (class "Default")
      (node (ref "CON5") (pin "1") (pinfunction "+12V_1") (pintype "passive"))
    )
    (net (code "53") (name "unconnected-(CON8-+12V-Pad1)") (class "Default")
      (node (ref "CON8") (pin "1") (pinfunction "+12V_1") (pintype "passive"))
    )
    (net (code "54") (name "unconnected-(CON10-Pad1)") (class "Default")
      (node (ref "CON10") (pin "1") (pinfunction "1_1") (pintype "passive"))
    )
    (net (code "55") (name "unconnected-(CON10-Pad2)") (class "Default")
      (node (ref "CON10") (pin "2") (pinfunction "2_2") (pintype "passive"))
    )
    (net (code "56") (name "unconnected-(CON10-Pad7)") (class "Default")
      (node (ref "CON10") (pin "7") (pinfunction "7_7") (pintype "passive"))
    )
    (net (code "57") (name "unconnected-(CON10-Pad8)") (class "Default")
      (node (ref "CON10") (pin "8") (pinfunction "8_8") (pintype "passive"))
    )
    (net (code "58") (name "unconnected-(CON10-SHIELD1-Pad9)") (class "Default")
      (node (ref "CON10") (pin "9") (pinfunction "SHIELD1_9") (pintype "passive"))
    )
    (net (code "59") (name "unconnected-(CON10-SHIELD2-Pad10)") (class "Default")
      (node (ref "CON10") (pin "10") (pinfunction "SHIELD2_10") (pintype "passive"))
    )
    (net (code "60") (name "unconnected-(IC2-2A-Pad7)") (class "Default")
      (node (ref "IC2") (pin "7") (pinfunction "2A_7") (pintype "bidirectional"))
    )
    (net (code "61") (name "unconnected-(IC2-2Y-Pad6)") (class "Default")
      (node (ref "IC2") (pin "6") (pinfunction "2Y_6") (pintype "bidirectional"))
    )
    (net (code "62") (name "unconnected-(IC2-3,4EN-Pad9)") (class "Default")
      (node (ref "IC2") (pin "9") (pinfunction "3,4EN_9") (pintype "bidirectional"))
    )
    (net (code "63") (name "unconnected-(IC2-3A-Pad10)") (class "Default")
      (node (ref "IC2") (pin "10") (pinfunction "3A_10") (pintype "bidirectional"))
    )
    (net (code "64") (name "unconnected-(IC2-3Y-Pad11)") (class "Default")
      (node (ref "IC2") (pin "11") (pinfunction "3Y_11") (pintype "bidirectional"))
    )
    (net (code "65") (name "unconnected-(IC2-4A-Pad15)") (class "Default")
      (node (ref "IC2") (pin "15") (pinfunction "4A_15") (pintype "bidirectional"))
    )
    (net (code "66") (name "unconnected-(IC2-4Y-Pad14)") (class "Default")
      (node (ref "IC2") (pin "14") (pinfunction "4Y_14") (pintype "bidirectional"))
    )
    (net (code "67") (name "unconnected-(IC2-GND2-Pad5)") (class "Default")
      (node (ref "IC2") (pin "5") (pinfunction "GND2_5") (pintype "bidirectional"))
    )
    (net (code "68") (name "unconnected-(IC2-GND3-Pad13)") (class "Default")
      (node (ref "IC2") (pin "13") (pinfunction "GND3_13") (pintype "bidirectional"))
    )
    (net (code "69") (name "unconnected-(IC2-GND4-Pad12)") (class "Default")
      (node (ref "IC2") (pin "12") (pinfunction "GND4_12") (pintype "bidirectional"))
    )
    (net (code "70") (name "unconnected-(IC3-DIN2-Pad10)") (class "Default")
      (node (ref "IC3") (pin "10") (pinfunction "DIN2_10") (pintype "bidirectional"))
    )
    (net (code "71") (name "unconnected-(IC3-DOUT2-Pad7)") (class "Default")
      (node (ref "IC3") (pin "7") (pinfunction "DOUT2_7") (pintype "bidirectional"))
    )
    (net (code "72") (name "unconnected-(IC3-RIN2-Pad8)") (class "Default")
      (node (ref "IC3") (pin "8") (pinfunction "RIN2_8") (pintype "bidirectional"))
    )
    (net (code "73") (name "unconnected-(IC3-ROUT2-Pad9)") (class "Default")
      (node (ref "IC3") (pin "9") (pinfunction "ROUT2_9") (pintype "bidirectional"))
    )
    (net (code "74") (name "unconnected-(IC4-3IN+-Pad10)") (class "Default")
      (node (ref "IC4") (pin "10") (pinfunction "3IN+_10") (pintype "bidirectional"))
    )
    (net (code "75") (name "unconnected-(IC4-3IN--Pad9)") (class "Default")
      (node (ref "IC4") (pin "9") (pinfunction "3IN-_9") (pintype "bidirectional"))
    )
    (net (code "76") (name "unconnected-(IC4-3OUT-Pad8)") (class "Default")
      (node (ref "IC4") (pin "8") (pinfunction "3OUT_8") (pintype "bidirectional"))
    )
    (net (code "77") (name "unconnected-(IC5-3IN+-Pad10)") (class "Default")
      (node (ref "IC5") (pin "10") (pinfunction "3IN+_10") (pintype "bidirectional"))
    )
    (net (code "78") (name "unconnected-(IC5-3IN--Pad9)") (class "Default")
      (node (ref "IC5") (pin "9") (pinfunction "3IN-_9") (pintype "bidirectional"))
    )
    (net (code "79") (name "unconnected-(IC5-3OUT-Pad8)") (class "Default")
      (node (ref "IC5") (pin "8") (pinfunction "3OUT_8") (pintype "bidirectional"))
    )
    (net (code "80") (name "unconnected-(STEERING-WHEEL-Pad5)") (class "Default")
      (node (ref "STEERING-WHEEL") (pin "5") (pinfunction "5_5") (pintype "passive"))
    )
    (net (code "81") (name "unconnected-(STEERING-WHEEL-Pad6)") (class "Default")
      (node (ref "STEERING-WHEEL") (pin "6") (pinfunction "6_6") (pintype "passive"))
    )
    (net (code "82") (name "unconnected-(STEERING-WHEEL-Pad7)") (class "Default")
      (node (ref "STEERING-WHEEL") (pin "7") (pinfunction "7_7") (pintype "passive"))
    )
    (net (code "83") (name "unconnected-(STEERING-WHEEL-Pad8)") (class "Default")
      (node (ref "STEERING-WHEEL") (pin "8") (pinfunction "8_8") (pintype "passive"))
    )
    (net (code "84") (name "unconnected-(UC1-PC3(ADC3)-Pad26)") (class "Default")
      (node (ref "UC1") (pin "26") (pinfunction "PC3(ADC3)_26") (pintype "bidirectional"))
    )
    (net (code "85") (name "unconnected-(UC1-PC4(ADC4{slash}SDA)-Pad27)") (class "Default")
      (node (ref "UC1") (pin "27") (pinfunction "PC4(ADC4/SDA)_27") (pintype "bidirectional"))
    )
    (net (code "86") (name "unconnected-(UC1-PC5(ADC5{slash}SCL)-Pad28)") (class "Default")
      (node (ref "UC1") (pin "28") (pinfunction "PC5(ADC5/SCL)_28") (pintype "bidirectional"))
    )
    (net (code "87") (name "unconnected-(UC1-PD6(AIN0)-Pad12)") (class "Default")
      (node (ref "UC1") (pin "12") (pinfunction "PD6(AIN0)_12") (pintype "bidirectional"))
    )
  )
)
